# 01-Antennas.net
KiCad netlist of a schematic drawn in Altium Designer
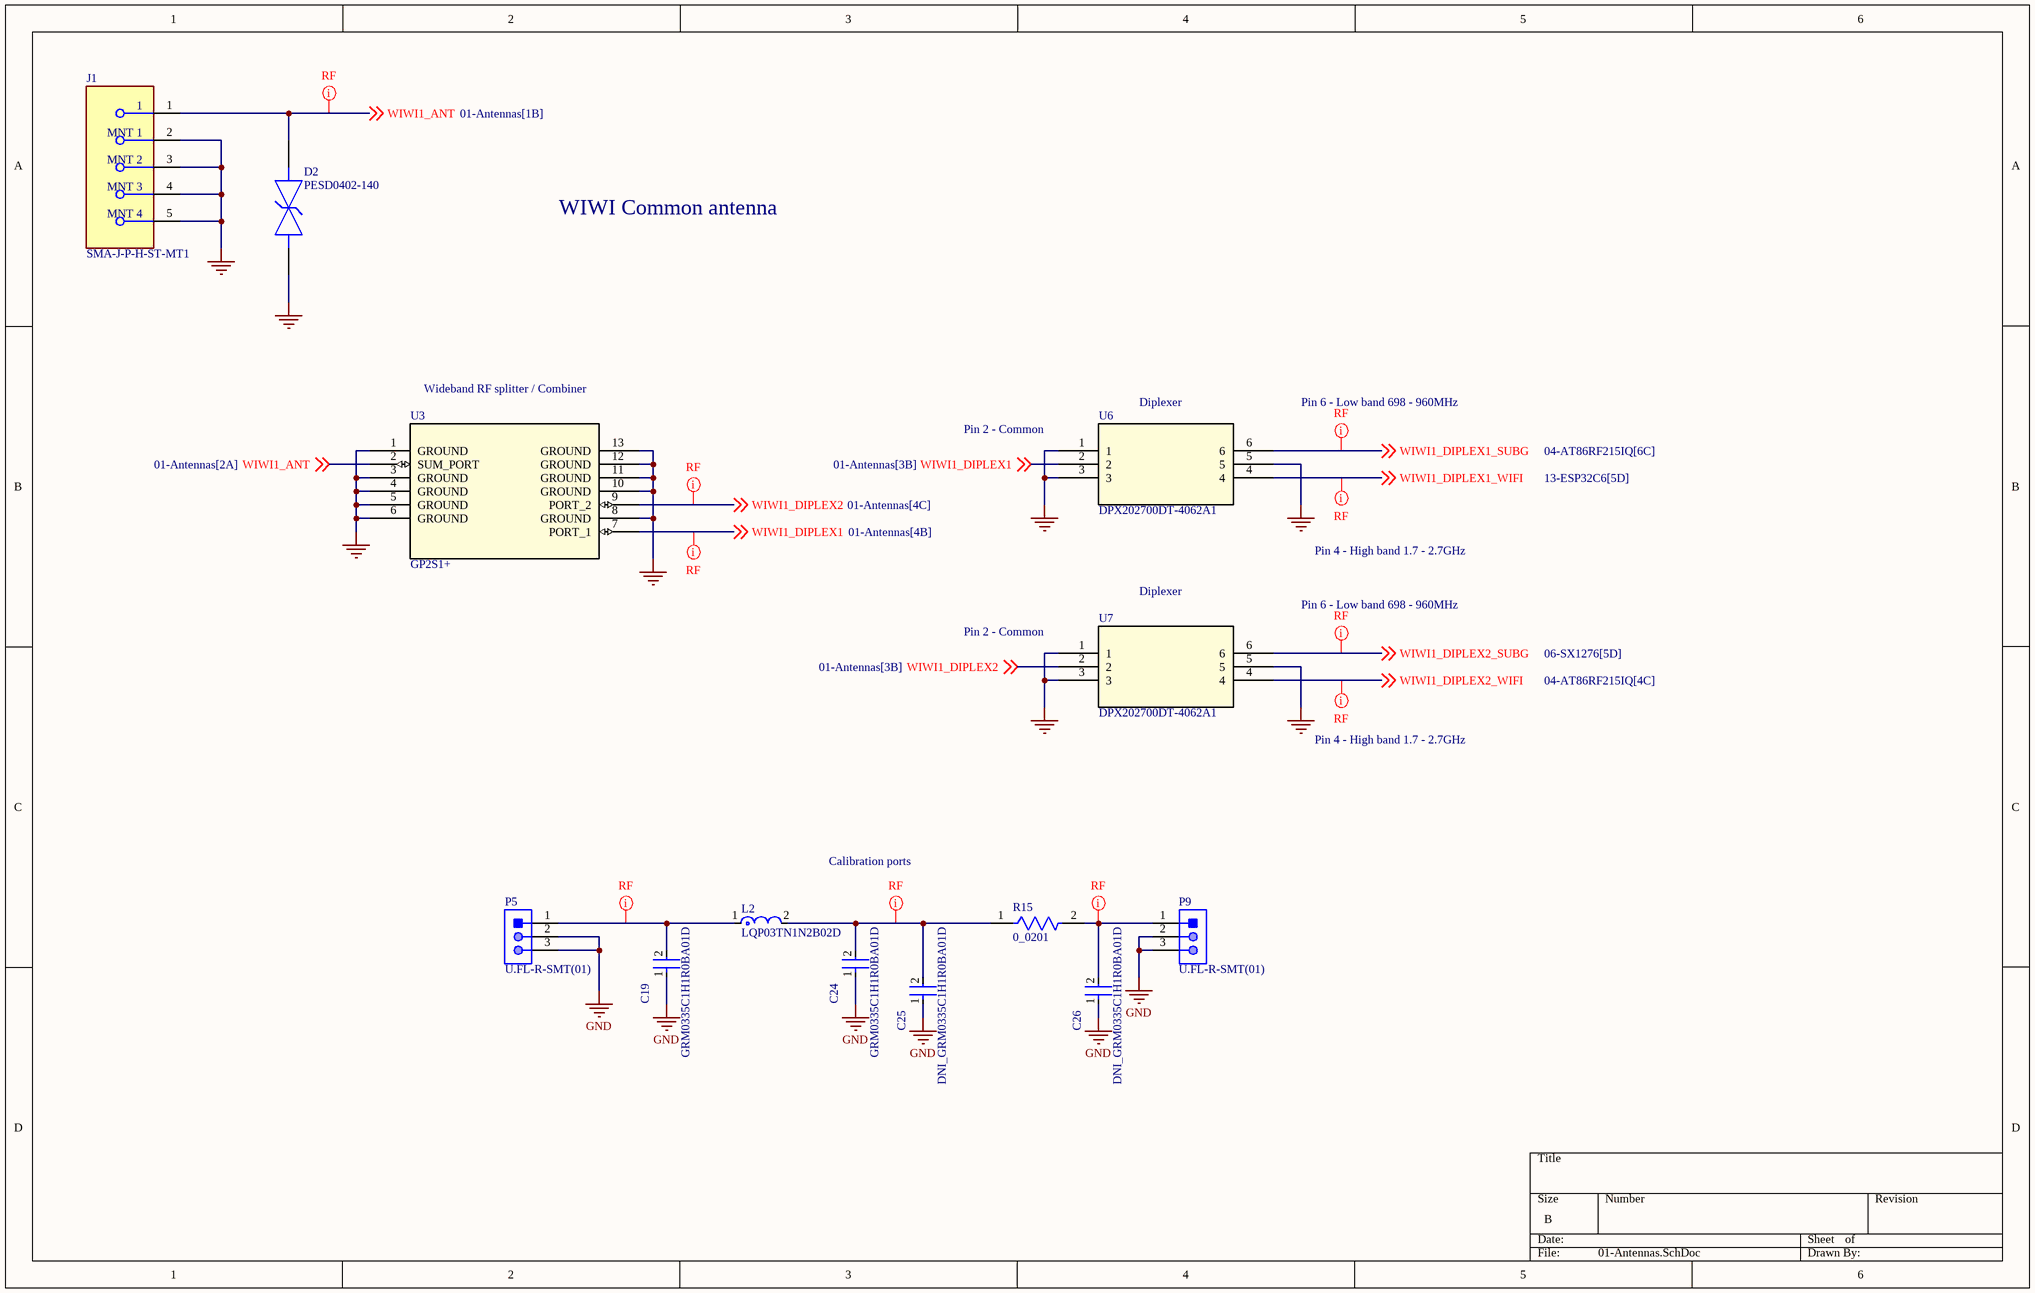
[diagram p0: 01-Antennas.SchDoc]

(export (version "E")
  (design (tool "Eeschema 10.0.6"))
  (components
    (comp (ref "C19")
      (value "GRM0335C1H1R0BA01D")
      (footprint "FP-GRM033-0_03-IPC_C")
      (description "Chip Multilayer Ceramic Capacitors for General Purpose, 0201, 1.0pF, C0G, 30ppm/°C, 0.1pF, 50V")
      (libsource (lib "Altium Content Vault") (part "b4654b650e69147ec39a6b967a45e02"))
    )
    (comp (ref "C24")
      (value "GRM0335C1H1R0BA01D")
      (footprint "FP-GRM033-0_03-IPC_C")
      (description "Chip Multilayer Ceramic Capacitors for General Purpose, 0201, 1.0pF, C0G, 30ppm/°C, 0.1pF, 50V")
      (libsource (lib "Altium Content Vault") (part "b4654b650e69147ec39a6b967a45e02"))
    )
    (comp (ref "C25")
      (value "DNI_GRM0335C1H1R0BA01D")
      (footprint "FP-GRM033-0_03-IPC_C")
      (description "Chip Multilayer Ceramic Capacitors for General Purpose, 0201, 1.0pF, C0G, 30ppm/°C, 0.1pF, 50V")
      (libsource (lib "Altium Content Vault") (part "b4654b650e69147ec39a6b967a45e02"))
    )
    (comp (ref "C26")
      (value "DNI_GRM0335C1H1R0BA01D")
      (footprint "FP-GRM033-0_03-IPC_C")
      (description "Chip Multilayer Ceramic Capacitors for General Purpose, 0201, 1.0pF, C0G, 30ppm/°C, 0.1pF, 50V")
      (libsource (lib "Altium Content Vault") (part "b4654b650e69147ec39a6b967a45e02"))
    )
    (comp (ref "D2")
      (value "PESD0402-140")
      (footprint "FP-PESD0402-MFG")
      (description "TVS DIODE 14V 40V 0402")
      (fields
        (field (name "OCTOPART") "https://octopart.com/pesd0402-140-littelfuse-74215061")
        (field (name "MANUFACTURER") "Littelfuse Inc.")
      )
      (libsource (lib "Altium Content Vault") (part "edccc070dd5cba1f9372128faf3915e"))
    )
    (comp (ref "J1")
      (value "SMA-J-P-H-ST-MT1")
      (footprint "FP-SMA-J-P-H-ST-MT1-MFG")
      (description "CONN SMA JACK STR 50 OHM SMD")
      (libsource (lib "Altium Content Vault") (part "9c40ac4d87bbbe9fcb330bd20f98ca3"))
    )
    (comp (ref "L2")
      (value "LQP03TN1N2B02D")
      (footprint "FP-LQP03TG_02-IPC_A")
      (description "Film type RF Inductor 1.2nH ±0.1nH 750mA 0.1Ω 0201 (0603)")
      (libsource (lib "Altium Content Vault") (part "4cc4b267dca4c8e51f7102f422741d8"))
    )
    (comp (ref "P5")
      (value "U.FL-R-SMT(01)")
      (footprint "HRS-U.FL-R-SMT(10)_V")
      (description "CONN RECPT ULTRA-MINI COAX SMD")
      (fields (field (name "MANUFACTURER") "Hirose Electric") (field (name "APPROVAL CATEGORY") "UL94V-0"))
      (libsource (lib "") (part "CN-1P-M-R3_1"))
    )
    (comp (ref "P9")
      (value "U.FL-R-SMT(01)")
      (footprint "HRS-U.FL-R-SMT(10)_V")
      (description "CONN RECPT ULTRA-MINI COAX SMD")
      (fields (field (name "MANUFACTURER") "Hirose Electric") (field (name "APPROVAL CATEGORY") "UL94V-0"))
      (libsource (lib "Altium Content Vault") (part "CN-1P-M-R3"))
    )
    (comp (ref "R15")
      (value "0_0201")
      (footprint "FP-RC_L0201-MFG")
      (description "RES SMD 0 OHM JUMPER 1/20W 0201")
      (fields
        (field (name "OCTOPART") "https://octopart.com/rc0201jr-070rl-yageo-43171986")
        (field (name "MANUFACTURER") "Yageo")
      )
      (libsource (lib "Altium Content Vault") (part "1029c3af85768c4190bb7ad29bc67b5"))
    )
    (comp (ref "U3")
      (value "GP2S1+")
      (footprint "DQ1225_MNC")
      (description "No Description Available")
      (libsource (lib "GP2S1&plus_") (part "GP2S1+"))
    )
    (comp (ref "U6")
      (value "DPX202700DT-4062A1")
      (footprint "RF_4060A1_TDK")
      (description "No Description Available")
      (libsource (lib "DPX202700DT-4062A1") (part "DPX202700DT-4062A1"))
    )
    (comp (ref "U7")
      (value "DPX202700DT-4062A1")
      (footprint "RF_4060A1_TDK")
      (description "No Description Available")
      (libsource (lib "DPX202700DT-4062A1") (part "DPX202700DT-4062A1"))
    )
  )
  (nets
    (net (code "1") (name "GND") (class "Default")
      (node (ref "C19") (pin "1") (pinfunction "1_1") (pintype "passive"))
      (node (ref "C24") (pin "1") (pinfunction "1_1") (pintype "passive"))
      (node (ref "C25") (pin "1") (pinfunction "1_1") (pintype "passive"))
      (node (ref "C26") (pin "1") (pinfunction "1_1") (pintype "passive"))
      (node (ref "D2") (pin "1") (pinfunction "1_1") (pintype "passive"))
      (node (ref "J1") (pin "2") (pinfunction "MNT_1_2") (pintype "passive"))
      (node (ref "J1") (pin "3") (pinfunction "MNT_2_3") (pintype "passive"))
      (node (ref "J1") (pin "4") (pinfunction "MNT_3_4") (pintype "passive"))
      (node (ref "J1") (pin "5") (pinfunction "MNT_4_5") (pintype "passive"))
      (node (ref "P5") (pin "2") (pinfunction "2_2") (pintype "passive"))
      (node (ref "P5") (pin "3") (pinfunction "3_3") (pintype "passive"))
      (node (ref "P9") (pin "2") (pinfunction "2_2") (pintype "passive"))
      (node (ref "P9") (pin "3") (pinfunction "3_3") (pintype "passive"))
      (node (ref "U3") (pin "1") (pinfunction "GROUND_1") (pintype "power_in"))
      (node (ref "U3") (pin "10") (pinfunction "GROUND_10") (pintype "power_in"))
      (node (ref "U3") (pin "11") (pinfunction "GROUND_11") (pintype "power_in"))
      (node (ref "U3") (pin "12") (pinfunction "GROUND_12") (pintype "power_in"))
      (node (ref "U3") (pin "13") (pinfunction "GROUND_13") (pintype "power_in"))
      (node (ref "U3") (pin "3") (pinfunction "GROUND_3") (pintype "power_in"))
      (node (ref "U3") (pin "4") (pinfunction "GROUND_4") (pintype "power_in"))
      (node (ref "U3") (pin "5") (pinfunction "GROUND_5") (pintype "power_in"))
      (node (ref "U3") (pin "6") (pinfunction "GROUND_6") (pintype "power_in"))
      (node (ref "U3") (pin "8") (pinfunction "GROUND_8") (pintype "power_in"))
      (node (ref "U6") (pin "1") (pinfunction "1_1") (pintype "passive"))
      (node (ref "U6") (pin "3") (pinfunction "3_3") (pintype "passive"))
      (node (ref "U6") (pin "5") (pinfunction "5_5") (pintype "passive"))
      (node (ref "U7") (pin "1") (pinfunction "1_1") (pintype "passive"))
      (node (ref "U7") (pin "3") (pinfunction "3_3") (pintype "passive"))
      (node (ref "U7") (pin "5") (pinfunction "5_5") (pintype "passive"))
    )
    (net (code "2") (name "Net-(C19-Pad2)") (class "Default")
      (node (ref "C19") (pin "2") (pinfunction "2_2") (pintype "passive"))
      (node (ref "L2") (pin "1") (pinfunction "1_1") (pintype "passive"))
      (node (ref "P5") (pin "1") (pinfunction "1_1") (pintype "passive"))
    )
    (net (code "3") (name "Net-(C24-Pad2)") (class "Default")
      (node (ref "C24") (pin "2") (pinfunction "2_2") (pintype "passive"))
      (node (ref "C25") (pin "2") (pinfunction "2_2") (pintype "passive"))
      (node (ref "L2") (pin "2") (pinfunction "2_2") (pintype "passive"))
      (node (ref "R15") (pin "1") (pinfunction "1_1") (pintype "passive"))
    )
    (net (code "4") (name "Net-(C26-Pad2)") (class "Default")
      (node (ref "C26") (pin "2") (pinfunction "2_2") (pintype "passive"))
      (node (ref "P9") (pin "1") (pinfunction "1_1") (pintype "passive"))
      (node (ref "R15") (pin "2") (pinfunction "2_2") (pintype "passive"))
    )
    (net (code "5") (name "WIWI1_ANT") (class "Default")
      (node (ref "D2") (pin "2") (pinfunction "2_2") (pintype "passive"))
      (node (ref "J1") (pin "1") (pinfunction "1_1") (pintype "passive"))
      (node (ref "U3") (pin "2") (pinfunction "SUM_PORT_2") (pintype "bidirectional"))
    )
    (net (code "6") (name "WIWI1_DIPLEX1") (class "Default")
      (node (ref "U3") (pin "7") (pinfunction "PORT_1_7") (pintype "bidirectional"))
      (node (ref "U6") (pin "2") (pinfunction "2_2") (pintype "passive"))
    )
    (net (code "7") (name "WIWI1_DIPLEX1_SUBG") (class "Default")
      (node (ref "U6") (pin "6") (pinfunction "6_6") (pintype "passive"))
    )
    (net (code "8") (name "WIWI1_DIPLEX1_WIFI") (class "Default")
      (node (ref "U6") (pin "4") (pinfunction "4_4") (pintype "passive"))
    )
    (net (code "9") (name "WIWI1_DIPLEX2") (class "Default")
      (node (ref "U3") (pin "9") (pinfunction "PORT_2_9") (pintype "bidirectional"))
      (node (ref "U7") (pin "2") (pinfunction "2_2") (pintype "passive"))
    )
    (net (code "10") (name "WIWI1_DIPLEX2_SUBG") (class "Default")
      (node (ref "U7") (pin "6") (pinfunction "6_6") (pintype "passive"))
    )
    (net (code "11") (name "WIWI1_DIPLEX2_WIFI") (class "Default")
      (node (ref "U7") (pin "4") (pinfunction "4_4") (pintype "passive"))
    )
  )
)
